# Source_Selector.net
KiCad netlist of a schematic drawn in Altium Designer
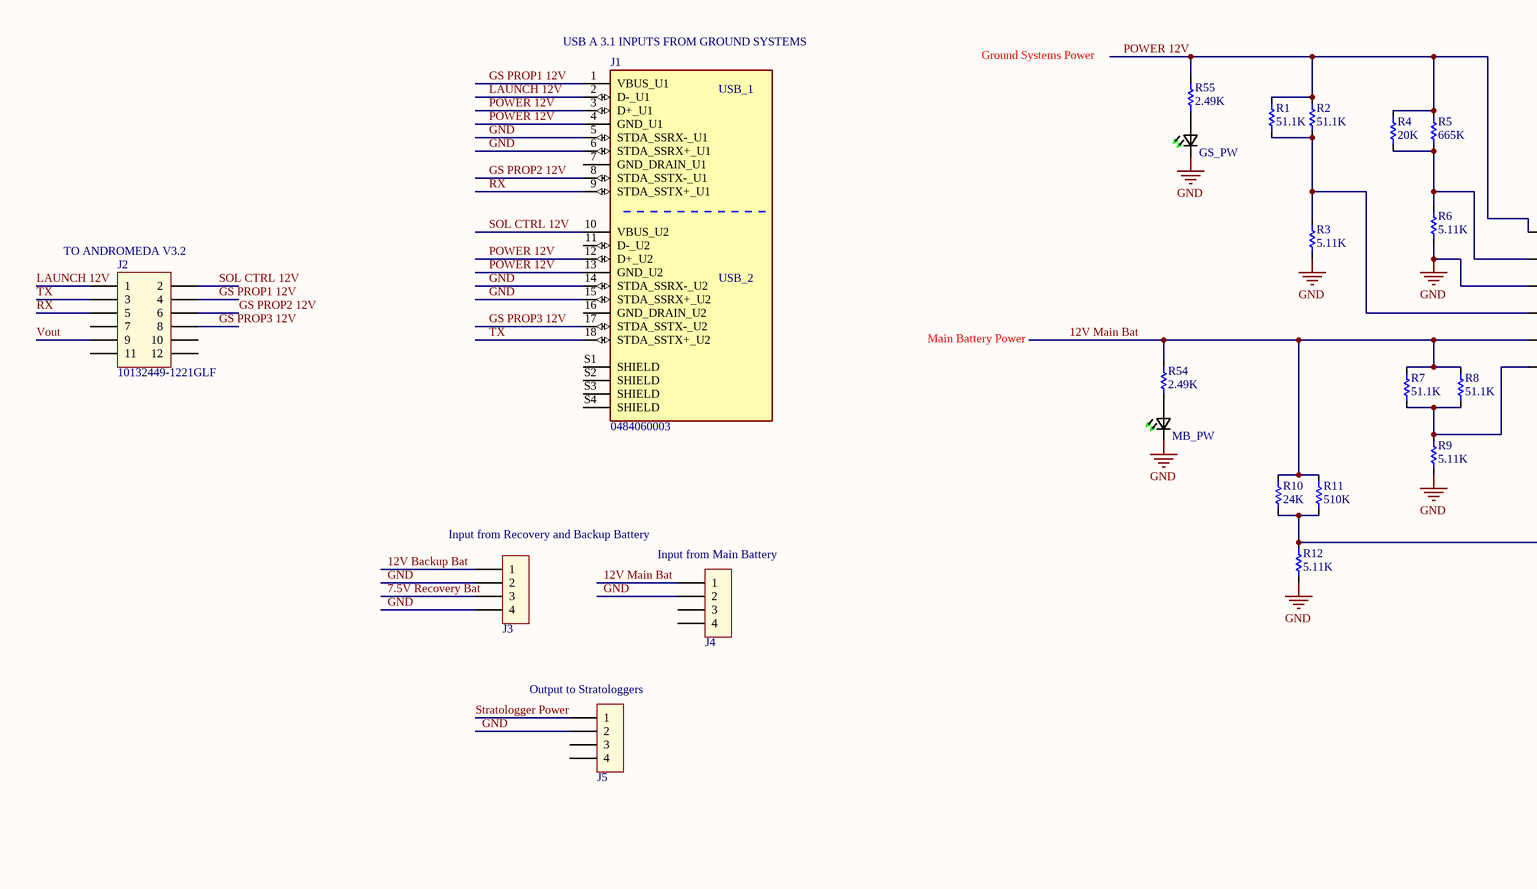
[diagram p0: Source_Selector.SchDoc, left]
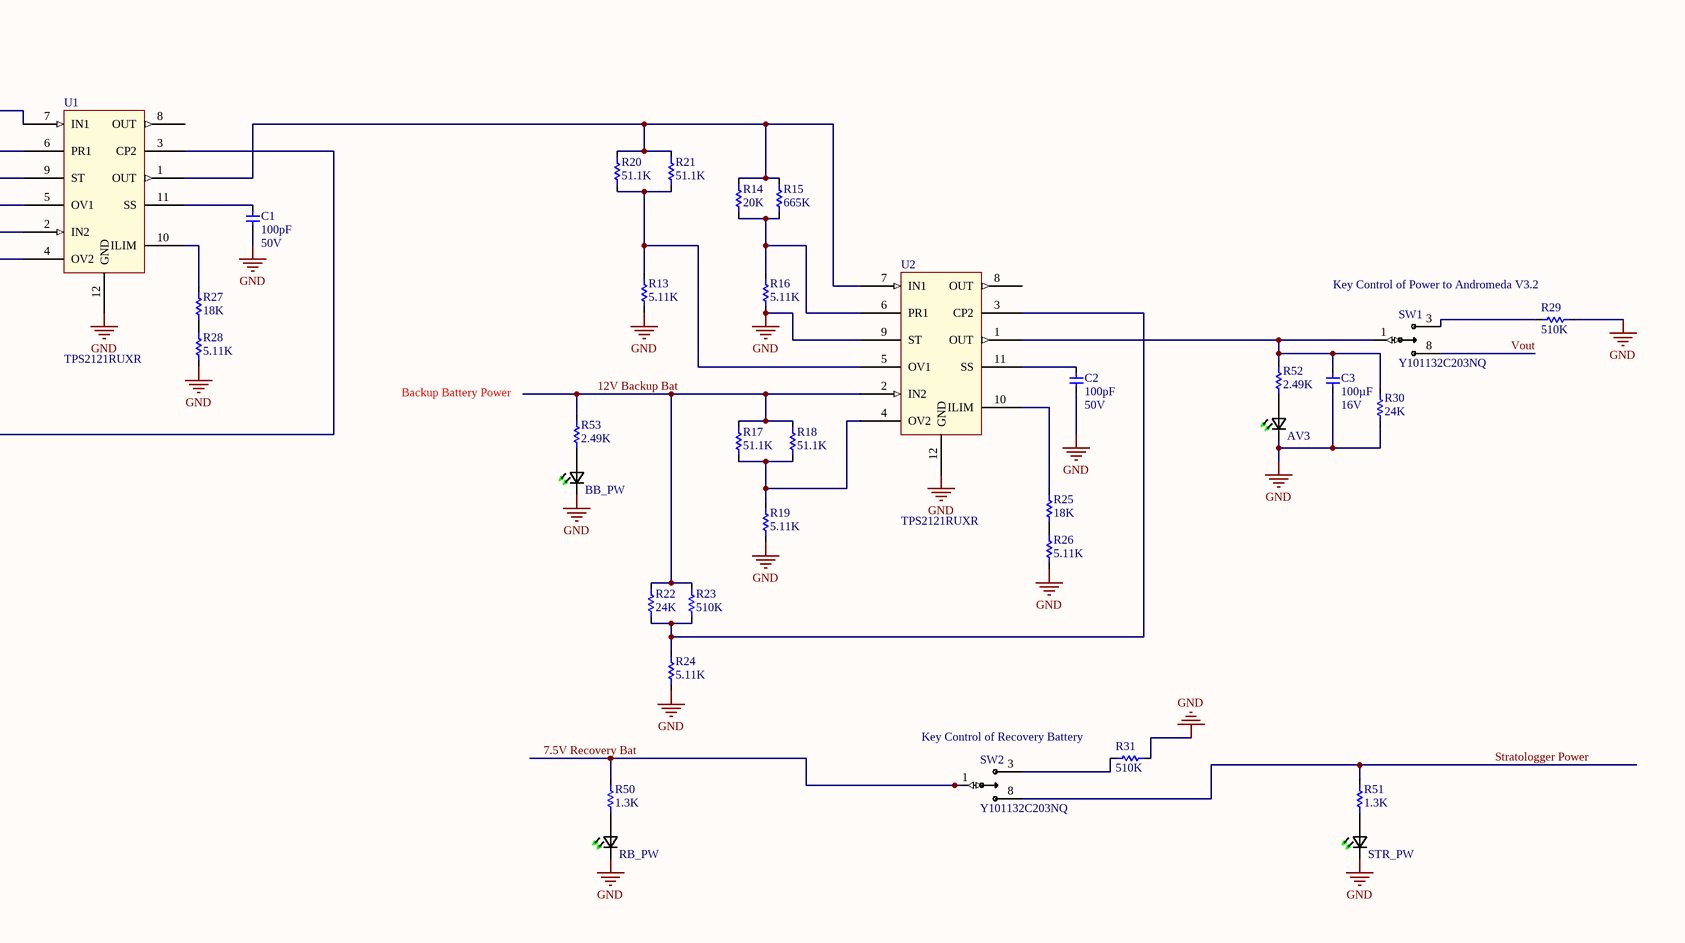
[diagram p1: Source_Selector.SchDoc, right]

(export (version "E")
  (design (tool "Eeschema 10.0.6"))
  (components
    (comp (ref "AV3")
      (value "LTST-C191KGKT")
      (footprint "LTST-C191KGKT")
      (description "LED GREEN CLEAR SMD 0603")
      (fields (field (name "MANUFACTURER") "Lite-On Inc."))
      (libsource (lib "Source Selector") (part "LTST-C191KGKT"))
    )
    (comp (ref "BB_PW")
      (value "LTST-C191KGKT")
      (footprint "LTST-C191KGKT")
      (description "LED GREEN CLEAR SMD 0603")
      (fields (field (name "MANUFACTURER") "Lite-On Inc."))
      (libsource (lib "Source Selector") (part "LTST-C191KGKT"))
    )
    (comp (ref "C1")
      (value "04025A101JAT2A")
      (footprint "0603[1608]")
      (description "CAP CER 100PF 50V C0G/NP0 0402")
      (fields
        (field (name "MANUFACTURER") "AVX Corporation")
        (field (name "TOLERANCE") "±5%")
        (field (name "CAPACITANCE") "100pF")
        (field (name "VOLTAGE - RATED") "50V")
      )
      (libsource (lib "Source Selector") (part "04025A101JAT2A"))
    )
    (comp (ref "C2")
      (value "04025A101JAT2A")
      (footprint "0603[1608]")
      (description "CAP CER 100PF 50V C0G/NP0 0402")
      (fields
        (field (name "MANUFACTURER") "AVX Corporation")
        (field (name "TOLERANCE") "±5%")
        (field (name "CAPACITANCE") "100pF")
        (field (name "VOLTAGE - RATED") "50V")
      )
      (libsource (lib "Source Selector") (part "04025A101JAT2A"))
    )
    (comp (ref "C3")
      (value "EMK325ABJ107MM-P")
      (footprint "CAPC3225X280N")
      (description "CAP CER 100UF 16V X5R 1210")
      (fields
        (field (name "MANUFACTURER") "Taiyo Yuden")
        (field (name "TOLERANCE") "±20%")
        (field (name "CAPACITANCE") "100µF")
        (field (name "VOLTAGE - RATED") "16V")
      )
      (libsource (lib "Source Selector") (part "EMK325ABJ107MM-P"))
    )
    (comp (ref "GS_PW")
      (value "LTST-C191KGKT")
      (footprint "LTST-C191KGKT")
      (description "LED GREEN CLEAR SMD 0603")
      (fields (field (name "MANUFACTURER") "Lite-On Inc."))
      (libsource (lib "Source Selector") (part "LTST-C191KGKT"))
    )
    (comp (ref "J1")
      (value "0484060003")
      (footprint "SnapEDApcb:MOLEX_0484060003")
      (fields (field (name "MF") "Molex"))
      (libsource (lib "Source Selector") (part "0484060003"))
    )
    (comp (ref "J2")
      (value "10132449-1221GLF")
      (footprint "10132449-1221GLF")
      (description "CONN HEADER R/A 12POS 3MM")
      (fields (field (name "MANUFACTURER") "Amphenol ICC (FCI)"))
      (libsource (lib "Source Selector") (part "10132449-1221GLF"))
    )
    (comp (ref "J3")
      (value "0430450400")
      (footprint "0430450400")
      (description "CONN HEADER R/A 4POS 3MM")
      (fields (field (name "MANUFACTURER") "Molex"))
      (libsource (lib "Source Selector") (part "0430450400"))
    )
    (comp (ref "J4")
      (value "0430450400")
      (footprint "0430450400")
      (description "CONN HEADER R/A 4POS 3MM")
      (fields (field (name "MANUFACTURER") "Molex"))
      (libsource (lib "Source Selector") (part "0430450400"))
    )
    (comp (ref "J5")
      (value "0430450400")
      (footprint "0430450400")
      (description "CONN HEADER R/A 4POS 3MM")
      (fields (field (name "MANUFACTURER") "Molex"))
      (libsource (lib "Source Selector") (part "0430450400"))
    )
    (comp (ref "MB_PW")
      (value "LTST-C191KGKT")
      (footprint "LTST-C191KGKT")
      (description "LED GREEN CLEAR SMD 0603")
      (fields (field (name "MANUFACTURER") "Lite-On Inc."))
      (libsource (lib "Source Selector") (part "LTST-C191KGKT"))
    )
    (comp (ref "R1")
      (value "MCT06030D5112BP500")
      (footprint "0603[1608]")
      (description "RES SMD 51.1KOHM 0.1% 1/10W 0603")
      (fields
        (field (name "TOLERANCE") "±0.1%")
        (field (name "MANUFACTURER") "Vishay Beyschlag/Draloric/BC Components")
        (field (name "RESISTANCE") "51.1K")
      )
      (libsource (lib "Source Selector") (part "MCT06030D5112BP500"))
    )
    (comp (ref "R2")
      (value "MCT06030D5112BP500")
      (footprint "0603[1608]")
      (description "RES SMD 51.1KOHM 0.1% 1/10W 0603")
      (fields
        (field (name "TOLERANCE") "±0.1%")
        (field (name "MANUFACTURER") "Vishay Beyschlag/Draloric/BC Components")
        (field (name "RESISTANCE") "51.1K")
      )
      (libsource (lib "Source Selector") (part "MCT06030D5112BP500"))
    )
    (comp (ref "R3")
      (value "RT0603BRD075K11L")
      (footprint "0603[1608]")
      (description "RES SMD 5.11KOHM 0.1% 1/10W 0603")
      (fields
        (field (name "TOLERANCE") "±0.1%")
        (field (name "MANUFACTURER") "Yageo")
        (field (name "RESISTANCE") "5.11K")
      )
      (libsource (lib "Source Selector") (part "RT0603BRD075K11L"))
    )
    (comp (ref "R4")
      (value "RNCF0603BTC20K0")
      (footprint "0603[1608]")
      (description "RES 20K OHM 0.1% 1/10W 0603")
      (fields
        (field (name "TOLERANCE") "±0.1%")
        (field (name "MANUFACTURER") "Stackpole Electronics Inc")
        (field (name "RESISTANCE") "20K")
      )
      (libsource (lib "Source Selector") (part "RNCF0603BTC20K0"))
    )
    (comp (ref "R5")
      (value "RMCF0603FT665K")
      (footprint "0603[1608]")
      (description "RES 665K OHM 1% 1/10W 0603")
      (fields
        (field (name "TOLERANCE") "±1%")
        (field (name "MANUFACTURER") "Stackpole Electronics Inc")
        (field (name "RESISTANCE") "665K")
      )
      (libsource (lib "Source Selector") (part "RMCF0603FT665K"))
    )
    (comp (ref "R6")
      (value "RT0603BRD075K11L")
      (footprint "0603[1608]")
      (description "RES SMD 5.11KOHM 0.1% 1/10W 0603")
      (fields
        (field (name "TOLERANCE") "±0.1%")
        (field (name "MANUFACTURER") "Yageo")
        (field (name "RESISTANCE") "5.11K")
      )
      (libsource (lib "Source Selector") (part "RT0603BRD075K11L"))
    )
    (comp (ref "R7")
      (value "MCT06030D5112BP500")
      (footprint "0603[1608]")
      (description "RES SMD 51.1KOHM 0.1% 1/10W 0603")
      (fields
        (field (name "TOLERANCE") "±0.1%")
        (field (name "MANUFACTURER") "Vishay Beyschlag/Draloric/BC Components")
        (field (name "RESISTANCE") "51.1K")
      )
      (libsource (lib "Source Selector") (part "MCT06030D5112BP500"))
    )
    (comp (ref "R8")
      (value "MCT06030D5112BP500")
      (footprint "0603[1608]")
      (description "RES SMD 51.1KOHM 0.1% 1/10W 0603")
      (fields
        (field (name "TOLERANCE") "±0.1%")
        (field (name "MANUFACTURER") "Vishay Beyschlag/Draloric/BC Components")
        (field (name "RESISTANCE") "51.1K")
      )
      (libsource (lib "Source Selector") (part "MCT06030D5112BP500"))
    )
    (comp (ref "R9")
      (value "RT0603BRD075K11L")
      (footprint "0603[1608]")
      (description "RES SMD 5.11KOHM 0.1% 1/10W 0603")
      (fields
        (field (name "TOLERANCE") "±0.1%")
        (field (name "MANUFACTURER") "Yageo")
        (field (name "RESISTANCE") "5.11K")
      )
      (libsource (lib "Source Selector") (part "RT0603BRD075K11L"))
    )
    (comp (ref "R10")
      (value "RT0603BRD0724KL")
      (footprint "0603[1608]")
      (description "RES SMD 24K OHM 0.1% 1/10W 0603")
      (fields
        (field (name "TOLERANCE") "±0.1%")
        (field (name "MANUFACTURER") "Yageo")
        (field (name "RESISTANCE") "24K")
      )
      (libsource (lib "Source Selector") (part "RT0603BRD0724KL"))
    )
    (comp (ref "R11")
      (value "CPF0603B510KE1")
      (footprint "0603[1608]")
      (description "RES SMD 510K OHM 0.1% 1/16W 0603")
      (fields
        (field (name "TOLERANCE") "±0.1%")
        (field (name "MANUFACTURER") "TE Connectivity Passive Product")
        (field (name "RESISTANCE") "510K")
      )
      (libsource (lib "Source Selector") (part "CPF0603B510KE1"))
    )
    (comp (ref "R12")
      (value "RT0603BRD075K11L")
      (footprint "0603[1608]")
      (description "RES SMD 5.11KOHM 0.1% 1/10W 0603")
      (fields
        (field (name "TOLERANCE") "±0.1%")
        (field (name "MANUFACTURER") "Yageo")
        (field (name "RESISTANCE") "5.11K")
      )
      (libsource (lib "Source Selector") (part "RT0603BRD075K11L"))
    )
    (comp (ref "R13")
      (value "RT0603BRD075K11L")
      (footprint "0603[1608]")
      (description "RES SMD 5.11KOHM 0.1% 1/10W 0603")
      (fields
        (field (name "TOLERANCE") "±0.1%")
        (field (name "MANUFACTURER") "Yageo")
        (field (name "RESISTANCE") "5.11K")
      )
      (libsource (lib "Source Selector") (part "RT0603BRD075K11L"))
    )
    (comp (ref "R14")
      (value "RNCF0603BTC20K0")
      (footprint "0603[1608]")
      (description "RES 20K OHM 0.1% 1/10W 0603")
      (fields
        (field (name "TOLERANCE") "±0.1%")
        (field (name "MANUFACTURER") "Stackpole Electronics Inc")
        (field (name "RESISTANCE") "20K")
      )
      (libsource (lib "Source Selector") (part "RNCF0603BTC20K0"))
    )
    (comp (ref "R15")
      (value "RMCF0603FT665K")
      (footprint "0603[1608]")
      (description "RES 665K OHM 1% 1/10W 0603")
      (fields
        (field (name "TOLERANCE") "±1%")
        (field (name "MANUFACTURER") "Stackpole Electronics Inc")
        (field (name "RESISTANCE") "665K")
      )
      (libsource (lib "Source Selector") (part "RMCF0603FT665K"))
    )
    (comp (ref "R16")
      (value "RT0603BRD075K11L")
      (footprint "0603[1608]")
      (description "RES SMD 5.11KOHM 0.1% 1/10W 0603")
      (fields
        (field (name "TOLERANCE") "±0.1%")
        (field (name "MANUFACTURER") "Yageo")
        (field (name "RESISTANCE") "5.11K")
      )
      (libsource (lib "Source Selector") (part "RT0603BRD075K11L"))
    )
    (comp (ref "R17")
      (value "MCT06030D5112BP500")
      (footprint "0603[1608]")
      (description "RES SMD 51.1KOHM 0.1% 1/10W 0603")
      (fields
        (field (name "TOLERANCE") "±0.1%")
        (field (name "MANUFACTURER") "Vishay Beyschlag/Draloric/BC Components")
        (field (name "RESISTANCE") "51.1K")
      )
      (libsource (lib "Source Selector") (part "MCT06030D5112BP500"))
    )
    (comp (ref "R18")
      (value "MCT06030D5112BP500")
      (footprint "0603[1608]")
      (description "RES SMD 51.1KOHM 0.1% 1/10W 0603")
      (fields
        (field (name "TOLERANCE") "±0.1%")
        (field (name "MANUFACTURER") "Vishay Beyschlag/Draloric/BC Components")
        (field (name "RESISTANCE") "51.1K")
      )
      (libsource (lib "Source Selector") (part "MCT06030D5112BP500"))
    )
    (comp (ref "R19")
      (value "RT0603BRD075K11L")
      (footprint "0603[1608]")
      (description "RES SMD 5.11KOHM 0.1% 1/10W 0603")
      (fields
        (field (name "TOLERANCE") "±0.1%")
        (field (name "MANUFACTURER") "Yageo")
        (field (name "RESISTANCE") "5.11K")
      )
      (libsource (lib "Source Selector") (part "RT0603BRD075K11L"))
    )
    (comp (ref "R20")
      (value "MCT06030D5112BP500")
      (footprint "0603[1608]")
      (description "RES SMD 51.1KOHM 0.1% 1/10W 0603")
      (fields
        (field (name "TOLERANCE") "±0.1%")
        (field (name "MANUFACTURER") "Vishay Beyschlag/Draloric/BC Components")
        (field (name "RESISTANCE") "51.1K")
      )
      (libsource (lib "Source Selector") (part "MCT06030D5112BP500"))
    )
    (comp (ref "R21")
      (value "MCT06030D5112BP500")
      (footprint "0603[1608]")
      (description "RES SMD 51.1KOHM 0.1% 1/10W 0603")
      (fields
        (field (name "TOLERANCE") "±0.1%")
        (field (name "MANUFACTURER") "Vishay Beyschlag/Draloric/BC Components")
        (field (name "RESISTANCE") "51.1K")
      )
      (libsource (lib "Source Selector") (part "MCT06030D5112BP500"))
    )
    (comp (ref "R22")
      (value "RT0603BRD0724KL")
      (footprint "0603[1608]")
      (description "RES SMD 24K OHM 0.1% 1/10W 0603")
      (fields
        (field (name "TOLERANCE") "±0.1%")
        (field (name "MANUFACTURER") "Yageo")
        (field (name "RESISTANCE") "24K")
      )
      (libsource (lib "Source Selector") (part "RT0603BRD0724KL"))
    )
    (comp (ref "R23")
      (value "CPF0603B510KE1")
      (footprint "0603[1608]")
      (description "RES SMD 510K OHM 0.1% 1/16W 0603")
      (fields
        (field (name "TOLERANCE") "±0.1%")
        (field (name "MANUFACTURER") "TE Connectivity Passive Product")
        (field (name "RESISTANCE") "510K")
      )
      (libsource (lib "Source Selector") (part "CPF0603B510KE1"))
    )
    (comp (ref "R24")
      (value "RT0603BRD075K11L")
      (footprint "0603[1608]")
      (description "RES SMD 5.11KOHM 0.1% 1/10W 0603")
      (fields
        (field (name "TOLERANCE") "±0.1%")
        (field (name "MANUFACTURER") "Yageo")
        (field (name "RESISTANCE") "5.11K")
      )
      (libsource (lib "Source Selector") (part "RT0603BRD075K11L"))
    )
    (comp (ref "R25")
      (value "RT0603BRE0718KL")
      (footprint "0603[1608]")
      (description "RES SMD 18K OHM 0.1% 1/10W 0603")
      (fields
        (field (name "TOLERANCE") "±0.1%")
        (field (name "MANUFACTURER") "Yageo")
        (field (name "RESISTANCE") "18K")
      )
      (libsource (lib "Source Selector") (part "RT0603BRE0718KL"))
    )
    (comp (ref "R26")
      (value "RT0603BRD075K11L")
      (footprint "0603[1608]")
      (description "RES SMD 5.11KOHM 0.1% 1/10W 0603")
      (fields
        (field (name "TOLERANCE") "±0.1%")
        (field (name "MANUFACTURER") "Yageo")
        (field (name "RESISTANCE") "5.11K")
      )
      (libsource (lib "Source Selector") (part "RT0603BRD075K11L"))
    )
    (comp (ref "R27")
      (value "RT0603BRE0718KL")
      (footprint "0603[1608]")
      (description "RES SMD 18K OHM 0.1% 1/10W 0603")
      (fields
        (field (name "TOLERANCE") "±0.1%")
        (field (name "MANUFACTURER") "Yageo")
        (field (name "RESISTANCE") "18K")
      )
      (libsource (lib "Source Selector") (part "RT0603BRE0718KL"))
    )
    (comp (ref "R28")
      (value "RT0603BRD075K11L")
      (footprint "0603[1608]")
      (description "RES SMD 5.11KOHM 0.1% 1/10W 0603")
      (fields
        (field (name "TOLERANCE") "±0.1%")
        (field (name "MANUFACTURER") "Yageo")
        (field (name "RESISTANCE") "5.11K")
      )
      (libsource (lib "Source Selector") (part "RT0603BRD075K11L"))
    )
    (comp (ref "R29")
      (value "CPF0603B510KE1")
      (footprint "0603[1608]")
      (description "RES SMD 510K OHM 0.1% 1/16W 0603")
      (fields
        (field (name "TOLERANCE") "±0.1%")
        (field (name "MANUFACTURER") "TE Connectivity Passive Product")
        (field (name "RESISTANCE") "510K")
      )
      (libsource (lib "Source Selector") (part "CPF0603B510KE1"))
    )
    (comp (ref "R30")
      (value "RT0603BRD0724KL")
      (footprint "0603[1608]")
      (description "RES SMD 24K OHM 0.1% 1/10W 0603")
      (fields
        (field (name "TOLERANCE") "±0.1%")
        (field (name "MANUFACTURER") "Yageo")
        (field (name "RESISTANCE") "24K")
      )
      (libsource (lib "Source Selector") (part "RT0603BRD0724KL"))
    )
    (comp (ref "R31")
      (value "CPF0603B510KE1")
      (footprint "0603[1608]")
      (description "RES SMD 510K OHM 0.1% 1/16W 0603")
      (fields
        (field (name "TOLERANCE") "±0.1%")
        (field (name "MANUFACTURER") "TE Connectivity Passive Product")
        (field (name "RESISTANCE") "510K")
      )
      (libsource (lib "Source Selector") (part "CPF0603B510KE1"))
    )
    (comp (ref "R50")
      (value "MCT06030C1301FP500")
      (footprint "0603[1608]")
      (description "RES SMD 1.3K OHM 1% 1/8W 0603")
      (fields
        (field (name "TOLERANCE") "±1%")
        (field (name "MANUFACTURER") "Vishay Beyschlag")
        (field (name "RESISTANCE") "1.3K")
      )
      (libsource (lib "Source Selector") (part "MCT06030C1301FP500"))
    )
    (comp (ref "R51")
      (value "MCT06030C1301FP500")
      (footprint "0603[1608]")
      (description "RES SMD 1.3K OHM 1% 1/8W 0603")
      (fields
        (field (name "TOLERANCE") "±1%")
        (field (name "MANUFACTURER") "Vishay Beyschlag")
        (field (name "RESISTANCE") "1.3K")
      )
      (libsource (lib "Source Selector") (part "MCT06030C1301FP500"))
    )
    (comp (ref "R52")
      (value "ERA-3AEB2491V")
      (footprint "0603[1608]")
      (description "RES SMD 2.49KOHM 0.1% 1/10W 0603")
      (fields
        (field (name "TOLERANCE") "±0.1%")
        (field (name "MANUFACTURER") "Panasonic Electronic Components")
        (field (name "RESISTANCE") "2.49K")
      )
      (libsource (lib "Source Selector") (part "ERA-3AEB2491V"))
    )
    (comp (ref "R53")
      (value "ERA-3AEB2491V")
      (footprint "0603[1608]")
      (description "RES SMD 2.49KOHM 0.1% 1/10W 0603")
      (fields
        (field (name "TOLERANCE") "±0.1%")
        (field (name "MANUFACTURER") "Panasonic Electronic Components")
        (field (name "RESISTANCE") "2.49K")
      )
      (libsource (lib "Source Selector") (part "ERA-3AEB2491V"))
    )
    (comp (ref "R54")
      (value "ERA-3AEB2491V")
      (footprint "0603[1608]")
      (description "RES SMD 2.49KOHM 0.1% 1/10W 0603")
      (fields
        (field (name "TOLERANCE") "±0.1%")
        (field (name "MANUFACTURER") "Panasonic Electronic Components")
        (field (name "RESISTANCE") "2.49K")
      )
      (libsource (lib "Source Selector") (part "ERA-3AEB2491V"))
    )
    (comp (ref "R55")
      (value "ERA-3AEB2491V")
      (footprint "0603[1608]")
      (description "RES SMD 2.49KOHM 0.1% 1/10W 0603")
      (fields
        (field (name "TOLERANCE") "±0.1%")
        (field (name "MANUFACTURER") "Panasonic Electronic Components")
        (field (name "RESISTANCE") "2.49K")
      )
      (libsource (lib "Source Selector") (part "ERA-3AEB2491V"))
    )
    (comp (ref "RB_PW")
      (value "LTST-C191KGKT")
      (footprint "LTST-C191KGKT")
      (description "LED GREEN CLEAR SMD 0603")
      (fields (field (name "MANUFACTURER") "Lite-On Inc."))
      (libsource (lib "Source Selector") (part "LTST-C191KGKT"))
    )
    (comp (ref "STR_PW")
      (value "LTST-C191KGKT")
      (footprint "LTST-C191KGKT")
      (description "LED GREEN CLEAR SMD 0603")
      (fields (field (name "MANUFACTURER") "Lite-On Inc."))
      (libsource (lib "Source Selector") (part "LTST-C191KGKT"))
    )
    (comp (ref "SW1")
      (value "Y101132C203NQ")
      (footprint "Y101132C203NQ")
      (description "SWITCH KEYLOCK 2POS SPDT 4A 125V")
      (fields (field (name "MANUFACTURER") "C&K"))
      (libsource (lib "Source Selector") (part "Y101132C203NQ"))
    )
    (comp (ref "SW2")
      (value "Y101132C203NQ")
      (footprint "Y101132C203NQ")
      (description "SWITCH KEYLOCK 2POS SPDT 4A 125V")
      (fields (field (name "MANUFACTURER") "C&K"))
      (libsource (lib "Source Selector") (part "Y101132C203NQ"))
    )
    (comp (ref "U1")
      (value "TPS2121RUXR")
      (footprint "IC_TPS2121RUXR")
      (description "PWR MGMT BATTERY MGMT")
      (libsource (lib "Source Selector") (part "TPS2121RUXR"))
    )
    (comp (ref "U2")
      (value "TPS2121RUXR")
      (footprint "IC_TPS2121RUXR")
      (description "PWR MGMT BATTERY MGMT")
      (libsource (lib "Source Selector") (part "TPS2121RUXR"))
    )
  )
  (nets
    (net (code "1") (name "/7.5V Recovery Bat") (class "Default")
      (node (ref "J3") (pin "3") (pinfunction "3_3") (pintype "passive"))
      (node (ref "R50") (pin "2") (pinfunction "2_2") (pintype "passive"))
      (node (ref "SW2") (pin "1") (pinfunction "1_1") (pintype "bidirectional"))
    )
    (net (code "2") (name "/12V Backup Bat") (class "Default")
      (node (ref "J3") (pin "1") (pinfunction "1_1") (pintype "passive"))
      (node (ref "R17") (pin "2") (pinfunction "2_2") (pintype "passive"))
      (node (ref "R18") (pin "2") (pinfunction "2_2") (pintype "passive"))
      (node (ref "R22") (pin "2") (pinfunction "2_2") (pintype "passive"))
      (node (ref "R23") (pin "2") (pinfunction "2_2") (pintype "passive"))
      (node (ref "R53") (pin "2") (pinfunction "2_2") (pintype "passive"))
      (node (ref "U2") (pin "2") (pinfunction "IN2_2") (pintype "input"))
    )
    (net (code "3") (name "/12V Main Bat") (class "Default")
      (node (ref "J4") (pin "1") (pinfunction "1_1") (pintype "passive"))
      (node (ref "R10") (pin "2") (pinfunction "2_2") (pintype "passive"))
      (node (ref "R11") (pin "2") (pinfunction "2_2") (pintype "passive"))
      (node (ref "R54") (pin "2") (pinfunction "2_2") (pintype "passive"))
      (node (ref "R7") (pin "2") (pinfunction "2_2") (pintype "passive"))
      (node (ref "R8") (pin "2") (pinfunction "2_2") (pintype "passive"))
      (node (ref "U1") (pin "2") (pinfunction "IN2_2") (pintype "input"))
    )
    (net (code "4") (name "/GS PROP1 12V") (class "Default")
      (node (ref "J1") (pin "1") (pinfunction "VBUS_U1_1") (pintype "power_in"))
      (node (ref "J2") (pin "4") (pinfunction "4_4") (pintype "passive"))
    )
    (net (code "5") (name "/GS PROP2 12V") (class "Default")
      (node (ref "J1") (pin "8") (pinfunction "STDA_SSTX-_U1_8") (pintype "bidirectional"))
      (node (ref "J2") (pin "6") (pinfunction "6_6") (pintype "passive"))
    )
    (net (code "6") (name "/GS PROP3 12V") (class "Default")
      (node (ref "J1") (pin "17") (pinfunction "STDA_SSTX-_U2_17") (pintype "bidirectional"))
      (node (ref "J2") (pin "8") (pinfunction "8_8") (pintype "passive"))
    )
    (net (code "7") (name "/LAUNCH 12V") (class "Default")
      (node (ref "J1") (pin "2") (pinfunction "D-_U1_2") (pintype "bidirectional"))
      (node (ref "J2") (pin "1") (pinfunction "1_1") (pintype "passive"))
    )
    (net (code "8") (name "/POWER 12V") (class "Default")
      (node (ref "J1") (pin "12") (pinfunction "D+_U2_12") (pintype "bidirectional"))
      (node (ref "J1") (pin "13") (pinfunction "GND_U2_13") (pintype "power_in"))
      (node (ref "J1") (pin "3") (pinfunction "D+_U1_3") (pintype "bidirectional"))
      (node (ref "J1") (pin "4") (pinfunction "GND_U1_4") (pintype "power_in"))
      (node (ref "R1") (pin "2") (pinfunction "2_2") (pintype "passive"))
      (node (ref "R2") (pin "2") (pinfunction "2_2") (pintype "passive"))
      (node (ref "R4") (pin "2") (pinfunction "2_2") (pintype "passive"))
      (node (ref "R5") (pin "2") (pinfunction "2_2") (pintype "passive"))
      (node (ref "R55") (pin "2") (pinfunction "2_2") (pintype "passive"))
      (node (ref "U1") (pin "7") (pinfunction "IN1_7") (pintype "input"))
    )
    (net (code "9") (name "/RX") (class "Default")
      (node (ref "J1") (pin "9") (pinfunction "STDA_SSTX+_U1_9") (pintype "bidirectional"))
      (node (ref "J2") (pin "5") (pinfunction "5_5") (pintype "passive"))
    )
    (net (code "10") (name "/SOL CTRL 12V") (class "Default")
      (node (ref "J1") (pin "10") (pinfunction "VBUS_U2_10") (pintype "power_in"))
      (node (ref "J2") (pin "2") (pinfunction "2_2") (pintype "passive"))
    )
    (net (code "11") (name "/Stratologger Power") (class "Default")
      (node (ref "J5") (pin "1") (pinfunction "1_1") (pintype "passive"))
      (node (ref "R51") (pin "2") (pinfunction "2_2") (pintype "passive"))
      (node (ref "SW2") (pin "8") (pinfunction "8_8") (pintype "power_in"))
    )
    (net (code "12") (name "/TX") (class "Default")
      (node (ref "J1") (pin "18") (pinfunction "STDA_SSTX+_U2_18") (pintype "bidirectional"))
      (node (ref "J2") (pin "3") (pinfunction "3_3") (pintype "passive"))
    )
    (net (code "13") (name "/Vout") (class "Default")
      (node (ref "J2") (pin "9") (pinfunction "9_9") (pintype "passive"))
      (node (ref "SW1") (pin "8") (pinfunction "8_8") (pintype "power_in"))
    )
    (net (code "14") (name "GND") (class "Default")
      (node (ref "AV3") (pin "1") (pinfunction "K2_1") (pintype "passive"))
      (node (ref "BB_PW") (pin "1") (pinfunction "K2_1") (pintype "passive"))
      (node (ref "C1") (pin "1") (pinfunction "1_1") (pintype "passive"))
      (node (ref "C2") (pin "1") (pinfunction "1_1") (pintype "passive"))
      (node (ref "C3") (pin "1") (pinfunction "1_1") (pintype "passive"))
      (node (ref "GS_PW") (pin "1") (pinfunction "K2_1") (pintype "passive"))
      (node (ref "J1") (pin "14") (pinfunction "STDA_SSRX-_U2_14") (pintype "bidirectional"))
      (node (ref "J1") (pin "15") (pinfunction "STDA_SSRX+_U2_15") (pintype "bidirectional"))
      (node (ref "J1") (pin "5") (pinfunction "STDA_SSRX-_U1_5") (pintype "bidirectional"))
      (node (ref "J1") (pin "6") (pinfunction "STDA_SSRX+_U1_6") (pintype "bidirectional"))
      (node (ref "J3") (pin "2") (pinfunction "2_2") (pintype "passive"))
      (node (ref "J3") (pin "4") (pinfunction "4_4") (pintype "passive"))
      (node (ref "J4") (pin "2") (pinfunction "2_2") (pintype "passive"))
      (node (ref "J5") (pin "2") (pinfunction "2_2") (pintype "passive"))
      (node (ref "MB_PW") (pin "1") (pinfunction "K2_1") (pintype "passive"))
      (node (ref "R12") (pin "1") (pinfunction "1_1") (pintype "passive"))
      (node (ref "R13") (pin "1") (pinfunction "1_1") (pintype "passive"))
      (node (ref "R16") (pin "1") (pinfunction "1_1") (pintype "passive"))
      (node (ref "R19") (pin "1") (pinfunction "1_1") (pintype "passive"))
      (node (ref "R24") (pin "1") (pinfunction "1_1") (pintype "passive"))
      (node (ref "R26") (pin "1") (pinfunction "1_1") (pintype "passive"))
      (node (ref "R28") (pin "1") (pinfunction "1_1") (pintype "passive"))
      (node (ref "R29") (pin "1") (pinfunction "1_1") (pintype "passive"))
      (node (ref "R3") (pin "1") (pinfunction "1_1") (pintype "passive"))
      (node (ref "R30") (pin "1") (pinfunction "1_1") (pintype "passive"))
      (node (ref "R31") (pin "1") (pinfunction "1_1") (pintype "passive"))
      (node (ref "R6") (pin "1") (pinfunction "1_1") (pintype "passive"))
      (node (ref "R9") (pin "1") (pinfunction "1_1") (pintype "passive"))
      (node (ref "RB_PW") (pin "1") (pinfunction "K2_1") (pintype "passive"))
      (node (ref "STR_PW") (pin "1") (pinfunction "K2_1") (pintype "passive"))
      (node (ref "U1") (pin "12") (pinfunction "GND_12") (pintype "passive"))
      (node (ref "U1") (pin "9") (pinfunction "ST_9") (pintype "passive"))
      (node (ref "U2") (pin "12") (pinfunction "GND_12") (pintype "passive"))
      (node (ref "U2") (pin "9") (pinfunction "ST_9") (pintype "passive"))
    )
    (net (code "15") (name "Net-(AV3-A2)") (class "Default")
      (node (ref "AV3") (pin "2") (pinfunction "A2_2") (pintype "passive"))
      (node (ref "R52") (pin "1") (pinfunction "1_1") (pintype "passive"))
    )
    (net (code "16") (name "Net-(BB_PW-A2)") (class "Default")
      (node (ref "BB_PW") (pin "2") (pinfunction "A2_2") (pintype "passive"))
      (node (ref "R53") (pin "1") (pinfunction "1_1") (pintype "passive"))
    )
    (net (code "17") (name "Net-(C3-Pad2)") (class "Default")
      (node (ref "C3") (pin "2") (pinfunction "2_2") (pintype "passive"))
      (node (ref "R30") (pin "2") (pinfunction "2_2") (pintype "passive"))
      (node (ref "R52") (pin "2") (pinfunction "2_2") (pintype "passive"))
      (node (ref "SW1") (pin "1") (pinfunction "1_1") (pintype "bidirectional"))
      (node (ref "U2") (pin "1") (pinfunction "OUT_1") (pintype "output"))
    )
    (net (code "18") (name "Net-(GS_PW-A2)") (class "Default")
      (node (ref "GS_PW") (pin "2") (pinfunction "A2_2") (pintype "passive"))
      (node (ref "R55") (pin "1") (pinfunction "1_1") (pintype "passive"))
    )
    (net (code "19") (name "Net-(MB_PW-A2)") (class "Default")
      (node (ref "MB_PW") (pin "2") (pinfunction "A2_2") (pintype "passive"))
      (node (ref "R54") (pin "1") (pinfunction "1_1") (pintype "passive"))
    )
    (net (code "20") (name "Net-(R25-Pad1)") (class "Default")
      (node (ref "R25") (pin "1") (pinfunction "1_1") (pintype "passive"))
      (node (ref "R26") (pin "2") (pinfunction "2_2") (pintype "passive"))
    )
    (net (code "21") (name "Net-(R27-Pad1)") (class "Default")
      (node (ref "R27") (pin "1") (pinfunction "1_1") (pintype "passive"))
      (node (ref "R28") (pin "2") (pinfunction "2_2") (pintype "passive"))
    )
    (net (code "22") (name "Net-(R29-Pad2)") (class "Default")
      (node (ref "R29") (pin "2") (pinfunction "2_2") (pintype "passive"))
      (node (ref "SW1") (pin "3") (pinfunction "3_3") (pintype "power_in"))
    )
    (net (code "23") (name "Net-(R31-Pad2)") (class "Default")
      (node (ref "R31") (pin "2") (pinfunction "2_2") (pintype "passive"))
      (node (ref "SW2") (pin "3") (pinfunction "3_3") (pintype "power_in"))
    )
    (net (code "24") (name "Net-(RB_PW-A2)") (class "Default")
      (node (ref "R50") (pin "1") (pinfunction "1_1") (pintype "passive"))
      (node (ref "RB_PW") (pin "2") (pinfunction "A2_2") (pintype "passive"))
    )
    (net (code "25") (name "Net-(STR_PW-A2)") (class "Default")
      (node (ref "R51") (pin "1") (pinfunction "1_1") (pintype "passive"))
      (node (ref "STR_PW") (pin "2") (pinfunction "A2_2") (pintype "passive"))
    )
    (net (code "26") (name "Net-(U1-CP2)") (class "Default")
      (node (ref "R10") (pin "1") (pinfunction "1_1") (pintype "passive"))
      (node (ref "R11") (pin "1") (pinfunction "1_1") (pintype "passive"))
      (node (ref "R12") (pin "2") (pinfunction "2_2") (pintype "passive"))
      (node (ref "U1") (pin "3") (pinfunction "CP2_3") (pintype "passive"))
    )
    (net (code "27") (name "Net-(U1-ILIM)") (class "Default")
      (node (ref "R27") (pin "2") (pinfunction "2_2") (pintype "passive"))
      (node (ref "U1") (pin "10") (pinfunction "ILIM_10") (pintype "passive"))
    )
    (net (code "28") (name "Net-(U1-OV1)") (class "Default")
      (node (ref "R1") (pin "1") (pinfunction "1_1") (pintype "passive"))
      (node (ref "R2") (pin "1") (pinfunction "1_1") (pintype "passive"))
      (node (ref "R3") (pin "2") (pinfunction "2_2") (pintype "passive"))
      (node (ref "U1") (pin "5") (pinfunction "OV1_5") (pintype "passive"))
    )
    (net (code "29") (name "Net-(U1-OV2)") (class "Default")
      (node (ref "R7") (pin "1") (pinfunction "1_1") (pintype "passive"))
      (node (ref "R8") (pin "1") (pinfunction "1_1") (pintype "passive"))
      (node (ref "R9") (pin "2") (pinfunction "2_2") (pintype "passive"))
      (node (ref "U1") (pin "4") (pinfunction "OV2_4") (pintype "passive"))
    )
    (net (code "30") (name "Net-(U1-PR1)") (class "Default")
      (node (ref "R4") (pin "1") (pinfunction "1_1") (pintype "passive"))
      (node (ref "R5") (pin "1") (pinfunction "1_1") (pintype "passive"))
      (node (ref "R6") (pin "2") (pinfunction "2_2") (pintype "passive"))
      (node (ref "U1") (pin "6") (pinfunction "PR1_6") (pintype "passive"))
    )
    (net (code "31") (name "Net-(U1-SS)") (class "Default")
      (node (ref "C1") (pin "2") (pinfunction "2_2") (pintype "passive"))
      (node (ref "U1") (pin "11") (pinfunction "SS_11") (pintype "passive"))
    )
    (net (code "32") (name "Net-(U2-CP2)") (class "Default")
      (node (ref "R22") (pin "1") (pinfunction "1_1") (pintype "passive"))
      (node (ref "R23") (pin "1") (pinfunction "1_1") (pintype "passive"))
      (node (ref "R24") (pin "2") (pinfunction "2_2") (pintype "passive"))
      (node (ref "U2") (pin "3") (pinfunction "CP2_3") (pintype "passive"))
    )
    (net (code "33") (name "Net-(U2-ILIM)") (class "Default")
      (node (ref "R25") (pin "2") (pinfunction "2_2") (pintype "passive"))
      (node (ref "U2") (pin "10") (pinfunction "ILIM_10") (pintype "passive"))
    )
    (net (code "34") (name "Net-(U2-IN1)") (class "Default")
      (node (ref "R14") (pin "2") (pinfunction "2_2") (pintype "passive"))
      (node (ref "R15") (pin "2") (pinfunction "2_2") (pintype "passive"))
      (node (ref "R20") (pin "2") (pinfunction "2_2") (pintype "passive"))
      (node (ref "R21") (pin "2") (pinfunction "2_2") (pintype "passive"))
      (node (ref "U1") (pin "1") (pinfunction "OUT_1") (pintype "output"))
      (node (ref "U2") (pin "7") (pinfunction "IN1_7") (pintype "input"))
    )
    (net (code "35") (name "Net-(U2-OV1)") (class "Default")
      (node (ref "R13") (pin "2") (pinfunction "2_2") (pintype "passive"))
      (node (ref "R20") (pin "1") (pinfunction "1_1") (pintype "passive"))
      (node (ref "R21") (pin "1") (pinfunction "1_1") (pintype "passive"))
      (node (ref "U2") (pin "5") (pinfunction "OV1_5") (pintype "passive"))
    )
    (net (code "36") (name "Net-(U2-OV2)") (class "Default")
      (node (ref "R17") (pin "1") (pinfunction "1_1") (pintype "passive"))
      (node (ref "R18") (pin "1") (pinfunction "1_1") (pintype "passive"))
      (node (ref "R19") (pin "2") (pinfunction "2_2") (pintype "passive"))
      (node (ref "U2") (pin "4") (pinfunction "OV2_4") (pintype "passive"))
    )
    (net (code "37") (name "Net-(U2-PR1)") (class "Default")
      (node (ref "R14") (pin "1") (pinfunction "1_1") (pintype "passive"))
      (node (ref "R15") (pin "1") (pinfunction "1_1") (pintype "passive"))
      (node (ref "R16") (pin "2") (pinfunction "2_2") (pintype "passive"))
      (node (ref "U2") (pin "6") (pinfunction "PR1_6") (pintype "passive"))
    )
    (net (code "38") (name "Net-(U2-SS)") (class "Default")
      (node (ref "C2") (pin "2") (pinfunction "2_2") (pintype "passive"))
      (node (ref "U2") (pin "11") (pinfunction "SS_11") (pintype "passive"))
    )
    (net (code "39") (name "unconnected-(J1-D-_U2-Pad11)") (class "Default")
      (node (ref "J1") (pin "11") (pinfunction "D-_U2_11") (pintype "bidirectional"))
    )
    (net (code "40") (name "unconnected-(J1-GND_DRAIN_U1-Pad7)") (class "Default")
      (node (ref "J1") (pin "7") (pinfunction "GND_DRAIN_U1_7") (pintype "power_in"))
    )
    (net (code "41") (name "unconnected-(J1-GND_DRAIN_U2-Pad16)") (class "Default")
      (node (ref "J1") (pin "16") (pinfunction "GND_DRAIN_U2_16") (pintype "power_in"))
    )
    (net (code "42") (name "unconnected-(J1-SHIELD-PadS1)") (class "Default")
      (node (ref "J1") (pin "S1") (pinfunction "SHIELD_S1") (pintype "passive"))
    )
    (net (code "43") (name "unconnected-(J1-SHIELD-PadS2)") (class "Default")
      (node (ref "J1") (pin "S2") (pinfunction "SHIELD_S2") (pintype "passive"))
    )
    (net (code "44") (name "unconnected-(J1-SHIELD-PadS3)") (class "Default")
      (node (ref "J1") (pin "S3") (pinfunction "SHIELD_S3") (pintype "passive"))
    )
    (net (code "45") (name "unconnected-(J1-SHIELD-PadS4)") (class "Default")
      (node (ref "J1") (pin "S4") (pinfunction "SHIELD_S4") (pintype "passive"))
    )
    (net (code "46") (name "unconnected-(J2-Pad7)") (class "Default")
      (node (ref "J2") (pin "7") (pinfunction "7_7") (pintype "passive"))
    )
    (net (code "47") (name "unconnected-(J2-Pad10)") (class "Default")
      (node (ref "J2") (pin "10") (pinfunction "10_10") (pintype "passive"))
    )
    (net (code "48") (name "unconnected-(J2-Pad11)") (class "Default")
      (node (ref "J2") (pin "11") (pinfunction "11_11") (pintype "passive"))
    )
    (net (code "49") (name "unconnected-(J2-Pad12)") (class "Default")
      (node (ref "J2") (pin "12") (pinfunction "12_12") (pintype "passive"))
    )
    (net (code "50") (name "unconnected-(J4-Pad3)") (class "Default")
      (node (ref "J4") (pin "3") (pinfunction "3_3") (pintype "passive"))
    )
    (net (code "51") (name "unconnected-(J4-Pad4)") (class "Default")
      (node (ref "J4") (pin "4") (pinfunction "4_4") (pintype "passive"))
    )
    (net (code "52") (name "unconnected-(J5-Pad3)") (class "Default")
      (node (ref "J5") (pin "3") (pinfunction "3_3") (pintype "passive"))
    )
    (net (code "53") (name "unconnected-(J5-Pad4)") (class "Default")
      (node (ref "J5") (pin "4") (pinfunction "4_4") (pintype "passive"))
    )
    (net (code "54") (name "unconnected-(U1-OUT-Pad8)") (class "Default")
      (node (ref "U1") (pin "8") (pinfunction "OUT_8") (pintype "output"))
    )
    (net (code "55") (name "unconnected-(U2-OUT-Pad8)") (class "Default")
      (node (ref "U2") (pin "8") (pinfunction "OUT_8") (pintype "output"))
    )
  )
)
